# Sheet1.net
KiCad netlist of a schematic drawn in Altium Designer
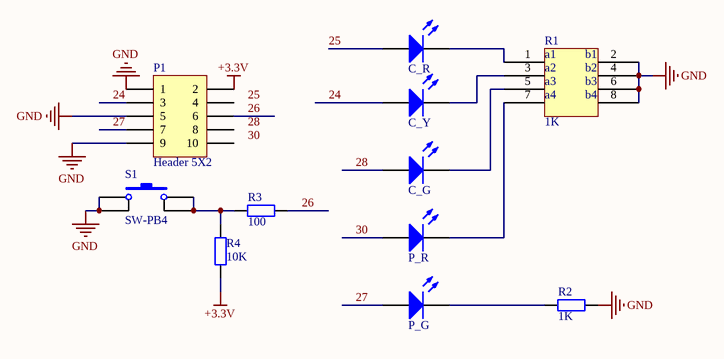
[diagram p0: Sheet1.SchDoc]

(export (version "E")
  (design (tool "Eeschema 10.0.6"))
  (components
    (comp (ref "C_G")
      (value "LED0")
      (footprint "LED_0805")
      (description "发光二极管")
      (fields (field (name "PUBLISHER") "Altium Limited"))
      (libsource (lib "mylibs") (part "LED0"))
    )
    (comp (ref "C_R")
      (value "LED0")
      (footprint "LED_0805")
      (description "发光二极管")
      (fields (field (name "PUBLISHER") "Altium Limited"))
      (libsource (lib "mylibs") (part "LED0"))
    )
    (comp (ref "C_Y")
      (value "LED0")
      (footprint "LED_0805")
      (description "发光二极管")
      (fields (field (name "PUBLISHER") "Altium Limited"))
      (libsource (lib "mylibs") (part "LED0"))
    )
    (comp (ref "P1")
      (value "Header 5X2")
      (footprint "HDR5X2_A1")
      (description "接插件")
      (fields (field (name "PUBLISHER") "Altium Limited"))
      (libsource (lib "mylibs") (part "Header 5X2"))
    )
    (comp (ref "P_G")
      (value "LED0")
      (footprint "LED_0805")
      (description "发光二极管")
      (fields (field (name "PUBLISHER") "Altium Limited"))
      (libsource (lib "mylibs") (part "LED0"))
    )
    (comp (ref "P_R")
      (value "LED0")
      (footprint "LED_0805")
      (description "发光二极管")
      (fields (field (name "PUBLISHER") "Altium Limited"))
      (libsource (lib "mylibs") (part "LED0"))
    )
    (comp (ref "R1") (value "1K") (footprint "8P4R_0603") (libsource (lib "HypoLib") (part "res_8p4r")))
    (comp (ref "R2")
      (value "1K")
      (footprint "0805-2")
      (description "贴片电阻")
      (fields (field (name "Comment") "Res1") (field (name "PUBLISHER") "Altium Limited"))
      (libsource (lib "") (part "Res1_1"))
    )
    (comp (ref "R3")
      (value "100")
      (footprint "0805-2")
      (description "贴片电阻")
      (fields (field (name "Comment") "Res1") (field (name "PUBLISHER") "Altium Limited"))
      (libsource (lib "mylibs") (part "Res1"))
    )
    (comp (ref "R4")
      (value "10K")
      (footprint "0805-2")
      (description "贴片电阻")
      (fields (field (name "Comment") "Res1") (field (name "PUBLISHER") "Altium Limited"))
      (libsource (lib "") (part "Res1_2"))
    )
    (comp (ref "S1")
      (value "SW-PB4")
      (footprint "SW_PB4_A1")
      (description "微动开关")
      (fields (field (name "PUBLISHER") "Altium Limited"))
      (libsource (lib "mylibs") (part "SW-PB4"))
    )
  )
  (nets
    (net (code "1") (name "+3.3V") (class "Default")
      (node (ref "P1") (pin "2") (pinfunction "2_2") (pintype "passive"))
      (node (ref "R4") (pin "1") (pinfunction "1_1") (pintype "passive"))
    )
    (net (code "2") (name "/24") (class "Default")
      (node (ref "C_Y") (pin "1") (pinfunction "A_1") (pintype "passive"))
      (node (ref "P1") (pin "3") (pinfunction "3_3") (pintype "passive"))
    )
    (net (code "3") (name "/25") (class "Default")
      (node (ref "C_R") (pin "1") (pinfunction "A_1") (pintype "passive"))
    )
    (net (code "4") (name "/26") (class "Default")
      (node (ref "P1") (pin "6") (pinfunction "6_6") (pintype "passive"))
      (node (ref "R3") (pin "1") (pinfunction "1_1") (pintype "passive"))
    )
    (net (code "5") (name "/27") (class "Default")
      (node (ref "P1") (pin "7") (pinfunction "7_7") (pintype "passive"))
      (node (ref "P_G") (pin "1") (pinfunction "A_1") (pintype "passive"))
    )
    (net (code "6") (name "/28") (class "Default")
      (node (ref "C_G") (pin "1") (pinfunction "A_1") (pintype "passive"))
    )
    (net (code "7") (name "/30") (class "Default")
      (node (ref "P_R") (pin "1") (pinfunction "A_1") (pintype "passive"))
    )
    (net (code "8") (name "GND") (class "Default")
      (node (ref "P1") (pin "1") (pinfunction "1_1") (pintype "passive"))
      (node (ref "P1") (pin "5") (pinfunction "5_5") (pintype "passive"))
      (node (ref "P1") (pin "9") (pinfunction "9_9") (pintype "passive"))
      (node (ref "R1") (pin "2") (pintype "passive"))
      (node (ref "R1") (pin "4") (pintype "passive"))
      (node (ref "R1") (pin "6") (pintype "passive"))
      (node (ref "R1") (pin "8") (pintype "passive"))
      (node (ref "R2") (pin "2") (pinfunction "2_2") (pintype "passive"))
      (node (ref "S1") (pin "1") (pinfunction "1_1") (pintype "passive"))
      (node (ref "S1") (pin "4") (pinfunction "4_4") (pintype "passive"))
    )
    (net (code "9") (name "Net-(C_G-K)") (class "Default")
      (node (ref "C_G") (pin "2") (pinfunction "K_2") (pintype "passive"))
      (node (ref "R1") (pin "5") (pintype "passive"))
    )
    (net (code "10") (name "Net-(C_R-K)") (class "Default")
      (node (ref "C_R") (pin "2") (pinfunction "K_2") (pintype "passive"))
      (node (ref "R1") (pin "1") (pintype "passive"))
    )
    (net (code "11") (name "Net-(C_Y-K)") (class "Default")
      (node (ref "C_Y") (pin "2") (pinfunction "K_2") (pintype "passive"))
      (node (ref "R1") (pin "3") (pintype "passive"))
    )
    (net (code "12") (name "Net-(P_G-K)") (class "Default")
      (node (ref "P_G") (pin "2") (pinfunction "K_2") (pintype "passive"))
      (node (ref "R2") (pin "1") (pinfunction "1_1") (pintype "passive"))
    )
    (net (code "13") (name "Net-(P_R-K)") (class "Default")
      (node (ref "P_R") (pin "2") (pinfunction "K_2") (pintype "passive"))
      (node (ref "R1") (pin "7") (pintype "passive"))
    )
    (net (code "14") (name "Net-(R3-Pad2)") (class "Default")
      (node (ref "R3") (pin "2") (pinfunction "2_2") (pintype "passive"))
      (node (ref "R4") (pin "2") (pinfunction "2_2") (pintype "passive"))
      (node (ref "S1") (pin "2") (pinfunction "2_2") (pintype "passive"))
      (node (ref "S1") (pin "3") (pinfunction "3_3") (pintype "passive"))
    )
    (net (code "15") (name "unconnected-(P1-Pad4)") (class "Default")
      (node (ref "P1") (pin "4") (pinfunction "4_4") (pintype "passive"))
    )
    (net (code "16") (name "unconnected-(P1-Pad8)") (class "Default")
      (node (ref "P1") (pin "8") (pinfunction "8_8") (pintype "passive"))
    )
    (net (code "17") (name "unconnected-(P1-Pad10)") (class "Default")
      (node (ref "P1") (pin "10") (pinfunction "10_10") (pintype "passive"))
    )
  )
)
